# RS485Comm.net
KiCad netlist of a schematic drawn in Altium Designer
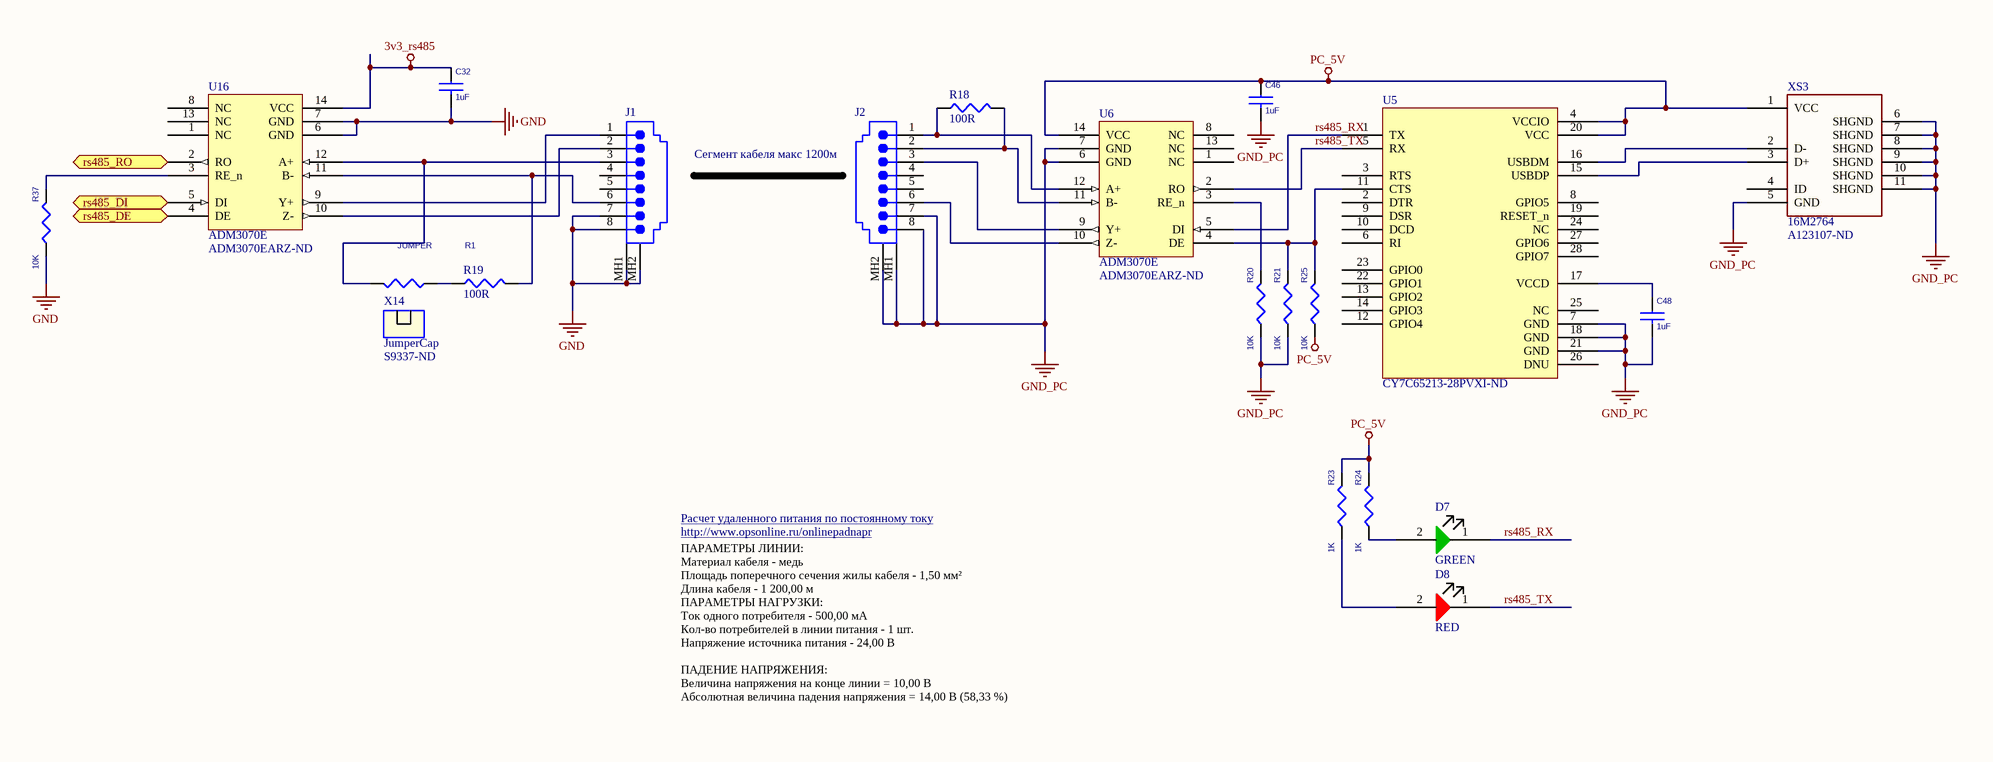
[diagram p0: RS485Comm.SchDoc]

(export (version "E")
  (design (tool "Eeschema 10.0.6"))
  (components
    (comp (ref "C32")
      (value "1uF")
      (footprint "CAPC2012X09M")
      (description "MLCC; 1uF; 25V; X7R; ±10%; SMD; 0805;")
      (libsource (lib "Capacitors") (part "CAP_SMD_1uF_10%"))
    )
    (comp (ref "C46")
      (value "1uF")
      (footprint "CAPC2012X09M")
      (description "MLCC; 1uF; 25V; X7R; ±10%; SMD; 0805;")
      (libsource (lib "Capacitors") (part "CAP_SMD_1uF_10%"))
    )
    (comp (ref "C48")
      (value "1uF")
      (footprint "CAPC2012X09M")
      (description "MLCC; 1uF; 25V; X7R; ±10%; SMD; 0805;")
      (libsource (lib "Capacitors") (part "CAP_SMD_1uF_10%"))
    )
    (comp (ref "D7")
      (value "GREEN")
      (footprint "DIOC2012X11N")
      (libsource (lib "Passive") (part "LED_GREEN"))
    )
    (comp (ref "D8") (value "RED") (footprint "DIOC2012X11N") (libsource (lib "Passive") (part "LED_RED")))
    (comp (ref "J1")
      (value "RJ-45")
      (footprint "RJ-45_PCB")
      (description "Jack Modular Connector 8p8c (RJ45, Ethernet) Vertical Unshielded Cat3")
      (libsource (lib "Connectors") (part "RJ-45"))
    )
    (comp (ref "J2")
      (value "RJ-45_1")
      (footprint "RJ-45_PCB")
      (description "Jack Modular Connector 8p8c (RJ45, Ethernet) 90° Angle (Right) Unshielded Cat3")
      (libsource (lib "Connectors") (part "RJ-45_1"))
    )
    (comp (ref "R1")
      (value "JUMPER")
      (footprint "RESC2013X06M_CMEASURE")
      (description "RES 0.0 OHM 1/8W JUMP 0805 SMD")
      (libsource (lib "Resistors") (part "RES_SMD_0_CURRENT"))
    )
    (comp (ref "R18")
      (value "100R")
      (footprint "RESC2013X06M")
      (description "RES - 100 OHM, 1%, 1/8W, 0805 SMD")
      (libsource (lib "Resistors") (part "RES_SMD_100R_1%"))
    )
    (comp (ref "R19")
      (value "100R")
      (footprint "RESC2013X06M")
      (description "RES - 100 OHM, 1%, 1/8W, 0805 SMD")
      (libsource (lib "Resistors") (part "RES_SMD_100R_1%"))
    )
    (comp (ref "R20")
      (value "10K")
      (footprint "RESC2013X06M")
      (description "RES 10K OHM 1/8W 5% 0805 SMD")
      (libsource (lib "Resistors") (part "RES_SMD_10K_5%"))
    )
    (comp (ref "R21")
      (value "10K")
      (footprint "RESC2013X06M")
      (description "RES 10K OHM 1/8W 5% 0805 SMD")
      (libsource (lib "Resistors") (part "RES_SMD_10K_5%"))
    )
    (comp (ref "R23")
      (value "1K")
      (footprint "RESC2013X06M")
      (description "RES - 1K OHM, 5%, 1/8W, 0805 SMD")
      (libsource (lib "Resistors") (part "RES_SMD_1K_5%"))
    )
    (comp (ref "R24")
      (value "1K")
      (footprint "RESC2013X06M")
      (description "RES - 1K OHM, 5%, 1/8W, 0805 SMD")
      (libsource (lib "Resistors") (part "RES_SMD_1K_5%"))
    )
    (comp (ref "R25")
      (value "10K")
      (footprint "RESC2013X06M")
      (description "RES 10K OHM 1/8W 5% 0805 SMD")
      (libsource (lib "Resistors") (part "RES_SMD_10K_5%"))
    )
    (comp (ref "R37")
      (value "10K")
      (footprint "RESC2013X06M")
      (description "RES 10K OHM 1/8W 5% 0805 SMD")
      (libsource (lib "Resistors") (part "RES_SMD_10K_5%"))
    )
    (comp (ref "U5")
      (value "CY7C65213")
      (footprint "SOP65P780X200-28M")
      (fields (field (name "SUPPLIER PART NUMBER 1") "CY7C65213-28PVXI-ND"))
      (libsource (lib "TruthEar") (part "CY7C65213"))
    )
    (comp (ref "U6")
      (value "ADM3070E")
      (footprint "SOIC127P600X175-14N")
      (fields (field (name "SUPPLIER PART NUMBER 1") "ADM3070EARZ-ND"))
      (libsource (lib "TruthEar") (part "ADM3070E"))
    )
    (comp (ref "U16")
      (value "ADM3070E")
      (footprint "SOIC127P600X175-14N")
      (fields (field (name "SUPPLIER PART NUMBER 1") "ADM3070EARZ-ND"))
      (libsource (lib "") (part "ADM3070E_1"))
    )
    (comp (ref "X14")
      (value "JumperCap")
      (description "For BOM only")
      (fields (field (name "SUPPLIER PART NUMBER 1") "S9337-ND"))
      (libsource (lib "TruthEar") (part "JumperCap"))
    )
    (comp (ref "XS3")
      (value "16M2764")
      (footprint "USB_MINI_16M2764")
      (fields (field (name "SUPPLIER PART NUMBER 1") "A123107-ND"))
      (libsource (lib "Connectors") (part "USB_MINI_16M2764"))
    )
  )
  (nets
    (net (code "1") (name "/rs485_DE") (class "Default")
      (node (ref "U16") (pin "4") (pinfunction "DE_4") (pintype "passive"))
    )
    (net (code "2") (name "/rs485_DI") (class "Default")
      (node (ref "U16") (pin "5") (pinfunction "DI_5") (pintype "input"))
    )
    (net (code "3") (name "/rs485_RO") (class "Default")
      (node (ref "U16") (pin "2") (pinfunction "RO_2") (pintype "output"))
    )
    (net (code "4") (name "/rs485_RX") (class "Default")
      (node (ref "D7") (pin "1") (pinfunction "C_1") (pintype "passive"))
      (node (ref "U5") (pin "1") (pinfunction "TX_1") (pintype "power_in"))
      (node (ref "U6") (pin "5") (pinfunction "DI_5") (pintype "input"))
    )
    (net (code "5") (name "/rs485_TX") (class "Default")
      (node (ref "D8") (pin "1") (pinfunction "C_1") (pintype "passive"))
      (node (ref "U5") (pin "5") (pinfunction "RX_5") (pintype "power_in"))
      (node (ref "U6") (pin "2") (pinfunction "RO_2") (pintype "output"))
    )
    (net (code "6") (name "3v3_rs485") (class "Default")
      (node (ref "C32") (pin "1") (pinfunction "1_1") (pintype "passive"))
      (node (ref "U16") (pin "14") (pinfunction "VCC_14") (pintype "passive"))
    )
    (net (code "7") (name "GND") (class "Default")
      (node (ref "C32") (pin "2") (pinfunction "2_2") (pintype "passive"))
      (node (ref "J1") (pin "7") (pinfunction "7_7") (pintype "passive"))
      (node (ref "J1") (pin "8") (pinfunction "8_8") (pintype "passive"))
      (node (ref "J1") (pin "MH1") (pinfunction "Shield_MH1") (pintype "passive"))
      (node (ref "J1") (pin "MH2") (pinfunction "Shield_MH2") (pintype "passive"))
      (node (ref "R37") (pin "1") (pinfunction "1_1") (pintype "passive"))
      (node (ref "U16") (pin "6") (pinfunction "GND_6") (pintype "passive"))
      (node (ref "U16") (pin "7") (pinfunction "GND_7") (pintype "passive"))
    )
    (net (code "8") (name "GND_PC") (class "Default")
      (node (ref "C46") (pin "2") (pinfunction "2_2") (pintype "passive"))
      (node (ref "C48") (pin "2") (pinfunction "2_2") (pintype "passive"))
      (node (ref "J2") (pin "7") (pinfunction "7_7") (pintype "passive"))
      (node (ref "J2") (pin "8") (pinfunction "8_8") (pintype "passive"))
      (node (ref "J2") (pin "MH1") (pinfunction "Shield_MH1") (pintype "passive"))
      (node (ref "J2") (pin "MH2") (pinfunction "Shield_MH2") (pintype "passive"))
      (node (ref "R20") (pin "1") (pinfunction "1_1") (pintype "passive"))
      (node (ref "R21") (pin "1") (pinfunction "1_1") (pintype "passive"))
      (node (ref "U5") (pin "18") (pinfunction "GND_18") (pintype "power_in"))
      (node (ref "U5") (pin "21") (pinfunction "GND_21") (pintype "power_in"))
      (node (ref "U5") (pin "7") (pinfunction "GND_7") (pintype "power_in"))
      (node (ref "U6") (pin "6") (pinfunction "GND_6") (pintype "passive"))
      (node (ref "U6") (pin "7") (pinfunction "GND_7") (pintype "passive"))
      (node (ref "XS3") (pin "10") (pinfunction "SHGND_10") (pintype "passive"))
      (node (ref "XS3") (pin "11") (pinfunction "SHGND_11") (pintype "passive"))
      (node (ref "XS3") (pin "5") (pinfunction "GND_5") (pintype "passive"))
      (node (ref "XS3") (pin "6") (pinfunction "SHGND_6") (pintype "passive"))
      (node (ref "XS3") (pin "7") (pinfunction "SHGND_7") (pintype "passive"))
      (node (ref "XS3") (pin "8") (pinfunction "SHGND_8") (pintype "passive"))
      (node (ref "XS3") (pin "9") (pinfunction "SHGND_9") (pintype "passive"))
    )
    (net (code "9") (name "Net-(D7-A)") (class "Default")
      (node (ref "D7") (pin "2") (pinfunction "A_2") (pintype "passive"))
      (node (ref "R24") (pin "1") (pinfunction "1_1") (pintype "passive"))
    )
    (net (code "10") (name "Net-(D8-A)") (class "Default")
      (node (ref "D8") (pin "2") (pinfunction "A_2") (pintype "passive"))
      (node (ref "R23") (pin "1") (pinfunction "1_1") (pintype "passive"))
    )
    (net (code "11") (name "Net-(R1-Pad1)") (class "Default")
      (node (ref "R1") (pin "1") (pinfunction "1_1") (pintype "passive"))
      (node (ref "R19") (pin "1") (pinfunction "1_1") (pintype "passive"))
    )
    (net (code "12") (name "Net-(U5-CTS)") (class "Default")
      (node (ref "R21") (pin "2") (pinfunction "2_2") (pintype "passive"))
      (node (ref "R25") (pin "2") (pinfunction "2_2") (pintype "passive"))
      (node (ref "U5") (pin "11") (pinfunction "CTS_11") (pintype "power_in"))
      (node (ref "U6") (pin "4") (pinfunction "DE_4") (pintype "passive"))
    )
    (net (code "13") (name "Net-(U5-USBDM)") (class "Default")
      (node (ref "U5") (pin "16") (pinfunction "USBDM_16") (pintype "power_in"))
      (node (ref "XS3") (pin "2") (pinfunction "D-_2") (pintype "passive"))
    )
    (net (code "14") (name "Net-(U5-USBDP)") (class "Default")
      (node (ref "U5") (pin "15") (pinfunction "USBDP_15") (pintype "power_in"))
      (node (ref "XS3") (pin "3") (pinfunction "D+_3") (pintype "passive"))
    )
    (net (code "15") (name "Net-(U5-VCCD)") (class "Default")
      (node (ref "C48") (pin "1") (pinfunction "1_1") (pintype "passive"))
      (node (ref "U5") (pin "17") (pinfunction "VCCD_17") (pintype "power_in"))
    )
    (net (code "16") (name "Net-(U6-A+)") (class "Default")
      (node (ref "J2") (pin "1") (pinfunction "1_1") (pintype "passive"))
      (node (ref "R18") (pin "1") (pinfunction "1_1") (pintype "passive"))
      (node (ref "U6") (pin "12") (pinfunction "A+_12") (pintype "input"))
    )
    (net (code "17") (name "Net-(U6-B-)") (class "Default")
      (node (ref "J2") (pin "2") (pinfunction "2_2") (pintype "passive"))
      (node (ref "R18") (pin "2") (pinfunction "2_2") (pintype "passive"))
      (node (ref "U6") (pin "11") (pinfunction "B-_11") (pintype "input"))
    )
    (net (code "18") (name "Net-(U6-RE_n)") (class "Default")
      (node (ref "R20") (pin "2") (pinfunction "2_2") (pintype "passive"))
      (node (ref "U6") (pin "3") (pinfunction "RE_n_3") (pintype "passive"))
    )
    (net (code "19") (name "Net-(U6-Y+)") (class "Default")
      (node (ref "J2") (pin "3") (pinfunction "3_3") (pintype "passive"))
      (node (ref "U6") (pin "9") (pinfunction "Y+_9") (pintype "output"))
    )
    (net (code "20") (name "Net-(U6-Z-)") (class "Default")
      (node (ref "J2") (pin "6") (pinfunction "6_6") (pintype "passive"))
      (node (ref "U6") (pin "10") (pinfunction "Z-_10") (pintype "output"))
    )
    (net (code "21") (name "Net-(U16-A+)") (class "Default")
      (node (ref "J1") (pin "3") (pinfunction "3_3") (pintype "passive"))
      (node (ref "R1") (pin "2") (pinfunction "2_2") (pintype "passive"))
      (node (ref "U16") (pin "12") (pinfunction "A+_12") (pintype "input"))
    )
    (net (code "22") (name "Net-(U16-B-)") (class "Default")
      (node (ref "J1") (pin "6") (pinfunction "6_6") (pintype "passive"))
      (node (ref "R19") (pin "2") (pinfunction "2_2") (pintype "passive"))
      (node (ref "U16") (pin "11") (pinfunction "B-_11") (pintype "input"))
    )
    (net (code "23") (name "Net-(U16-RE_n)") (class "Default")
      (node (ref "R37") (pin "2") (pinfunction "2_2") (pintype "passive"))
      (node (ref "U16") (pin "3") (pinfunction "RE_n_3") (pintype "passive"))
    )
    (net (code "24") (name "Net-(U16-Y+)") (class "Default")
      (node (ref "J1") (pin "1") (pinfunction "1_1") (pintype "passive"))
      (node (ref "U16") (pin "9") (pinfunction "Y+_9") (pintype "output"))
    )
    (net (code "25") (name "Net-(U16-Z-)") (class "Default")
      (node (ref "J1") (pin "2") (pinfunction "2_2") (pintype "passive"))
      (node (ref "U16") (pin "10") (pinfunction "Z-_10") (pintype "output"))
    )
    (net (code "26") (name "PC_5V") (class "Default")
      (node (ref "C46") (pin "1") (pinfunction "1_1") (pintype "passive"))
      (node (ref "R23") (pin "2") (pinfunction "2_2") (pintype "passive"))
      (node (ref "R24") (pin "2") (pinfunction "2_2") (pintype "passive"))
      (node (ref "R25") (pin "1") (pinfunction "1_1") (pintype "passive"))
      (node (ref "U5") (pin "20") (pinfunction "VCC_20") (pintype "power_in"))
      (node (ref "U5") (pin "4") (pinfunction "VCCIO_4") (pintype "power_in"))
      (node (ref "U6") (pin "14") (pinfunction "VCC_14") (pintype "passive"))
      (node (ref "XS3") (pin "1") (pinfunction "VCC_1") (pintype "passive"))
    )
    (net (code "27") (name "unconnected-(J1-Pad4)") (class "Default")
      (node (ref "J1") (pin "4") (pinfunction "4_4") (pintype "passive"))
    )
    (net (code "28") (name "unconnected-(J1-Pad5)") (class "Default")
      (node (ref "J1") (pin "5") (pinfunction "5_5") (pintype "passive"))
    )
    (net (code "29") (name "unconnected-(J2-Pad4)") (class "Default")
      (node (ref "J2") (pin "4") (pinfunction "4_4") (pintype "passive"))
    )
    (net (code "30") (name "unconnected-(J2-Pad5)") (class "Default")
      (node (ref "J2") (pin "5") (pinfunction "5_5") (pintype "passive"))
    )
    (net (code "31") (name "unconnected-(U5-DCD-Pad10)") (class "Default")
      (node (ref "U5") (pin "10") (pinfunction "DCD_10") (pintype "power_in"))
    )
    (net (code "32") (name "unconnected-(U5-DNU-Pad26)") (class "Default")
      (node (ref "U5") (pin "26") (pinfunction "DNU_26") (pintype "power_in"))
    )
    (net (code "33") (name "unconnected-(U5-DSR-Pad9)") (class "Default")
      (node (ref "U5") (pin "9") (pinfunction "DSR_9") (pintype "power_in"))
    )
    (net (code "34") (name "unconnected-(U5-DTR-Pad2)") (class "Default")
      (node (ref "U5") (pin "2") (pinfunction "DTR_2") (pintype "power_in"))
    )
    (net (code "35") (name "unconnected-(U5-GPIO0-Pad23)") (class "Default")
      (node (ref "U5") (pin "23") (pinfunction "GPIO0_23") (pintype "power_in"))
    )
    (net (code "36") (name "unconnected-(U5-GPIO1-Pad22)") (class "Default")
      (node (ref "U5") (pin "22") (pinfunction "GPIO1_22") (pintype "power_in"))
    )
    (net (code "37") (name "unconnected-(U5-GPIO2-Pad13)") (class "Default")
      (node (ref "U5") (pin "13") (pinfunction "GPIO2_13") (pintype "power_in"))
    )
    (net (code "38") (name "unconnected-(U5-GPIO3-Pad14)") (class "Default")
      (node (ref "U5") (pin "14") (pinfunction "GPIO3_14") (pintype "power_in"))
    )
    (net (code "39") (name "unconnected-(U5-GPIO4-Pad12)") (class "Default")
      (node (ref "U5") (pin "12") (pinfunction "GPIO4_12") (pintype "power_in"))
    )
    (net (code "40") (name "unconnected-(U5-GPIO5-Pad8)") (class "Default")
      (node (ref "U5") (pin "8") (pinfunction "GPIO5_8") (pintype "power_in"))
    )
    (net (code "41") (name "unconnected-(U5-GPIO6-Pad27)") (class "Default")
      (node (ref "U5") (pin "27") (pinfunction "GPIO6_27") (pintype "power_in"))
    )
    (net (code "42") (name "unconnected-(U5-GPIO7-Pad28)") (class "Default")
      (node (ref "U5") (pin "28") (pinfunction "GPIO7_28") (pintype "power_in"))
    )
    (net (code "43") (name "unconnected-(U5-NC-Pad24)") (class "Default")
      (node (ref "U5") (pin "24") (pinfunction "NC_24") (pintype "power_in"))
    )
    (net (code "44") (name "unconnected-(U5-NC-Pad25)") (class "Default")
      (node (ref "U5") (pin "25") (pinfunction "NC_25") (pintype "power_in"))
    )
    (net (code "45") (name "unconnected-(U5-RESET_n-Pad19)") (class "Default")
      (node (ref "U5") (pin "19") (pinfunction "RESET_n_19") (pintype "power_in"))
    )
    (net (code "46") (name "unconnected-(U5-RI-Pad6)") (class "Default")
      (node (ref "U5") (pin "6") (pinfunction "RI_6") (pintype "power_in"))
    )
    (net (code "47") (name "unconnected-(U5-RTS-Pad3)") (class "Default")
      (node (ref "U5") (pin "3") (pinfunction "RTS_3") (pintype "power_in"))
    )
    (net (code "48") (name "unconnected-(U6-NC-Pad1)") (class "Default")
      (node (ref "U6") (pin "1") (pinfunction "NC_1") (pintype "passive"))
    )
    (net (code "49") (name "unconnected-(U6-NC-Pad8)") (class "Default")
      (node (ref "U6") (pin "8") (pinfunction "NC_8") (pintype "passive"))
    )
    (net (code "50") (name "unconnected-(U6-NC-Pad13)") (class "Default")
      (node (ref "U6") (pin "13") (pinfunction "NC_13") (pintype "passive"))
    )
    (net (code "51") (name "unconnected-(U16-NC-Pad1)") (class "Default")
      (node (ref "U16") (pin "1") (pinfunction "NC_1") (pintype "passive"))
    )
    (net (code "52") (name "unconnected-(U16-NC-Pad8)") (class "Default")
      (node (ref "U16") (pin "8") (pinfunction "NC_8") (pintype "passive"))
    )
    (net (code "53") (name "unconnected-(U16-NC-Pad13)") (class "Default")
      (node (ref "U16") (pin "13") (pinfunction "NC_13") (pintype "passive"))
    )
    (net (code "54") (name "unconnected-(XS3-ID-Pad4)") (class "Default")
      (node (ref "XS3") (pin "4") (pinfunction "ID_4") (pintype "passive"))
    )
  )
)
